# bmw.net
KiCad netlist of a schematic drawn in EAGLE
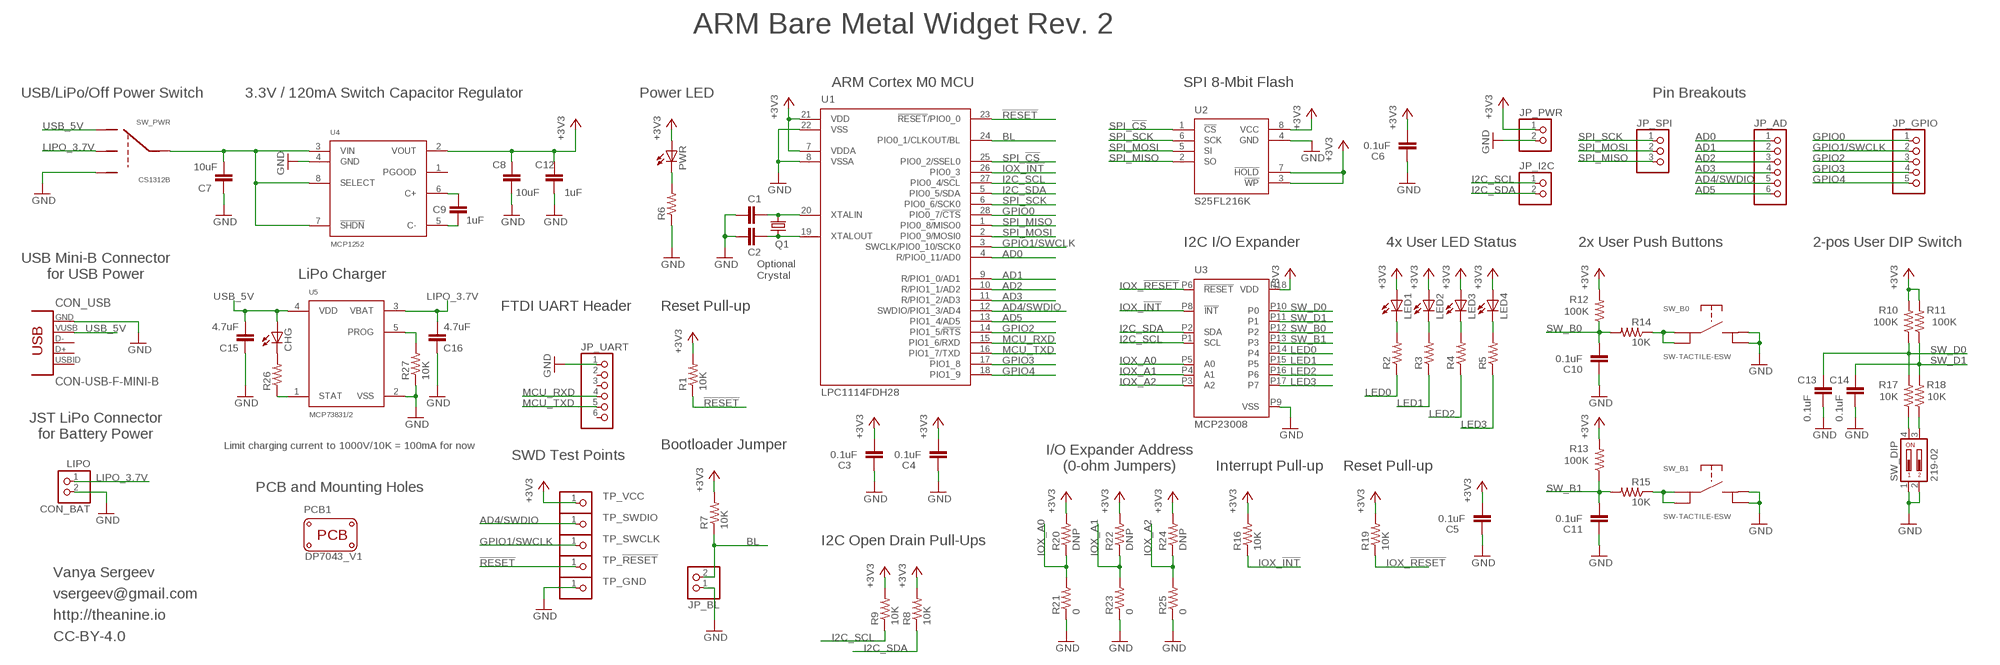
[diagram p0: schematic, sheet 1]

(export (version "E")
  (design (tool "Eeschema 10.0.6"))
  (components
    (comp (ref "C1")
      (value "C-EUC0805")
      (footprint "eagle-import:C0805")
      (libsource (lib "eagle-import") (part "C-EUC0805"))
    )
    (comp (ref "C2")
      (value "C-EUC0805")
      (footprint "eagle-import:C0805")
      (libsource (lib "eagle-import") (part "C-EUC0805"))
    )
    (comp (ref "C3")
      (value "0.1uF")
      (footprint "eagle-import:C0805")
      (libsource (lib "eagle-import") (part "C-EUC0805"))
    )
    (comp (ref "C4")
      (value "0.1uF")
      (footprint "eagle-import:C0805")
      (libsource (lib "eagle-import") (part "C-EUC0805"))
    )
    (comp (ref "C5")
      (value "0.1uF")
      (footprint "eagle-import:C0805")
      (libsource (lib "eagle-import") (part "C-EUC0805"))
    )
    (comp (ref "C6")
      (value "0.1uF")
      (footprint "eagle-import:C0805")
      (libsource (lib "eagle-import") (part "C-EUC0805"))
    )
    (comp (ref "C7")
      (value "10uF")
      (footprint "eagle-import:C1206")
      (libsource (lib "eagle-import") (part "C-EUC1206"))
    )
    (comp (ref "C8")
      (value "10uF")
      (footprint "eagle-import:C1206")
      (libsource (lib "eagle-import") (part "C-EUC1206"))
    )
    (comp (ref "C9")
      (value "1uF")
      (footprint "eagle-import:C0805")
      (libsource (lib "eagle-import") (part "C-EUC0805"))
    )
    (comp (ref "C10")
      (value "0.1uF")
      (footprint "eagle-import:C0805")
      (libsource (lib "eagle-import") (part "C-EUC0805"))
    )
    (comp (ref "C11")
      (value "0.1uF")
      (footprint "eagle-import:C0805")
      (libsource (lib "eagle-import") (part "C-EUC0805"))
    )
    (comp (ref "C12")
      (value "1uF")
      (footprint "eagle-import:C0805")
      (libsource (lib "eagle-import") (part "C-EUC0805"))
    )
    (comp (ref "C13")
      (value "0.1uF")
      (footprint "eagle-import:C0805")
      (libsource (lib "eagle-import") (part "C-EUC0805"))
    )
    (comp (ref "C14")
      (value "0.1uF")
      (footprint "eagle-import:C0805")
      (libsource (lib "eagle-import") (part "C-EUC0805"))
    )
    (comp (ref "C15")
      (value "4.7uF")
      (footprint "eagle-import:C0805")
      (libsource (lib "eagle-import") (part "C-EUC0805"))
    )
    (comp (ref "C16")
      (value "4.7uF")
      (footprint "eagle-import:C0805")
      (libsource (lib "eagle-import") (part "C-EUC0805"))
    )
    (comp (ref "CHG")
      (value "LEDCHIPLED_0805")
      (footprint "eagle-import:CHIPLED_0805")
      (libsource (lib "eagle-import") (part "LEDCHIPLED_0805"))
    )
    (comp (ref "CON_BAT")
      (value "LIPO")
      (footprint "eagle-import:JST-PH-2-SMT-RA")
      (libsource (lib "eagle-import") (part "JST_2PIN-SMT-RA"))
    )
    (comp (ref "CON_USB")
      (value "CON-USB-F-MINI-B")
      (footprint "eagle-import:CONN_USB_MINI-B")
      (libsource (lib "eagle-import") (part "CON-USB-F-MINI-B"))
    )
    (comp (ref "JP_AD")
      (value "PINHD-1X6")
      (footprint "eagle-import:1X06")
      (libsource (lib "eagle-import") (part "PINHD-1X6"))
    )
    (comp (ref "JP_BL")
      (value "PINHD-1X2")
      (footprint "eagle-import:1X02")
      (libsource (lib "eagle-import") (part "PINHD-1X2"))
    )
    (comp (ref "JP_GPIO")
      (value "PINHD-1X5")
      (footprint "eagle-import:1X05")
      (libsource (lib "eagle-import") (part "PINHD-1X5"))
    )
    (comp (ref "JP_I2C")
      (value "PINHD-1X2")
      (footprint "eagle-import:1X02")
      (libsource (lib "eagle-import") (part "PINHD-1X2"))
    )
    (comp (ref "JP_PWR")
      (value "PINHD-1X2")
      (footprint "eagle-import:1X02")
      (libsource (lib "eagle-import") (part "PINHD-1X2"))
    )
    (comp (ref "JP_SPI")
      (value "PINHD-1X3")
      (footprint "eagle-import:1X03")
      (libsource (lib "eagle-import") (part "PINHD-1X3"))
    )
    (comp (ref "JP_UART")
      (value "PINHD-1X6/90")
      (footprint "eagle-import:1X06_90")
      (libsource (lib "eagle-import") (part "PINHD-1X6/90"))
    )
    (comp (ref "LED1")
      (value "LEDCHIPLED_0805")
      (footprint "eagle-import:CHIPLED_0805")
      (libsource (lib "eagle-import") (part "LEDCHIPLED_0805"))
    )
    (comp (ref "LED2")
      (value "LEDCHIPLED_0805")
      (footprint "eagle-import:CHIPLED_0805")
      (libsource (lib "eagle-import") (part "LEDCHIPLED_0805"))
    )
    (comp (ref "LED3")
      (value "LEDCHIPLED_0805")
      (footprint "eagle-import:CHIPLED_0805")
      (libsource (lib "eagle-import") (part "LEDCHIPLED_0805"))
    )
    (comp (ref "LED4")
      (value "LEDCHIPLED_0805")
      (footprint "eagle-import:CHIPLED_0805")
      (libsource (lib "eagle-import") (part "LEDCHIPLED_0805"))
    )
    (comp (ref "PCB1")
      (value "PCB_DP_RECTANGLE-43X70")
      (footprint "eagle-import:DP7043_V1")
      (libsource (lib "eagle-import") (part "PCB_DP_RECTANGLE-43X70"))
    )
    (comp (ref "PWR")
      (value "LEDCHIPLED_0805")
      (footprint "eagle-import:CHIPLED_0805")
      (libsource (lib "eagle-import") (part "LEDCHIPLED_0805"))
    )
    (comp (ref "Q1")
      (value "CRYSTALHC49UP")
      (footprint "eagle-import:HC49UP")
      (libsource (lib "eagle-import") (part "CRYSTALHC49UP"))
    )
    (comp (ref "R1")
      (value "10K")
      (footprint "eagle-import:R0805")
      (libsource (lib "eagle-import") (part "R-US_R0805"))
    )
    (comp (ref "R2")
      (value "R-US_R0805")
      (footprint "eagle-import:R0805")
      (libsource (lib "eagle-import") (part "R-US_R0805"))
    )
    (comp (ref "R3")
      (value "R-US_R0805")
      (footprint "eagle-import:R0805")
      (libsource (lib "eagle-import") (part "R-US_R0805"))
    )
    (comp (ref "R4")
      (value "R-US_R0805")
      (footprint "eagle-import:R0805")
      (libsource (lib "eagle-import") (part "R-US_R0805"))
    )
    (comp (ref "R5")
      (value "R-US_R0805")
      (footprint "eagle-import:R0805")
      (libsource (lib "eagle-import") (part "R-US_R0805"))
    )
    (comp (ref "R6")
      (value "R-US_R0805")
      (footprint "eagle-import:R0805")
      (libsource (lib "eagle-import") (part "R-US_R0805"))
    )
    (comp (ref "R7")
      (value "10K")
      (footprint "eagle-import:R0805")
      (libsource (lib "eagle-import") (part "R-US_R0805"))
    )
    (comp (ref "R8")
      (value "10K")
      (footprint "eagle-import:R0805")
      (libsource (lib "eagle-import") (part "R-US_R0805"))
    )
    (comp (ref "R9")
      (value "10K")
      (footprint "eagle-import:R0805")
      (libsource (lib "eagle-import") (part "R-US_R0805"))
    )
    (comp (ref "R10")
      (value "100K")
      (footprint "eagle-import:R0805")
      (libsource (lib "eagle-import") (part "R-US_R0805"))
    )
    (comp (ref "R11")
      (value "100K")
      (footprint "eagle-import:R0805")
      (libsource (lib "eagle-import") (part "R-US_R0805"))
    )
    (comp (ref "R12")
      (value "100K")
      (footprint "eagle-import:R0805")
      (libsource (lib "eagle-import") (part "R-US_R0805"))
    )
    (comp (ref "R13")
      (value "100K")
      (footprint "eagle-import:R0805")
      (libsource (lib "eagle-import") (part "R-US_R0805"))
    )
    (comp (ref "R14")
      (value "10K")
      (footprint "eagle-import:R0805")
      (libsource (lib "eagle-import") (part "R-US_R0805"))
    )
    (comp (ref "R15")
      (value "10K")
      (footprint "eagle-import:R0805")
      (libsource (lib "eagle-import") (part "R-US_R0805"))
    )
    (comp (ref "R16")
      (value "10K")
      (footprint "eagle-import:R0805")
      (libsource (lib "eagle-import") (part "R-US_R0805"))
    )
    (comp (ref "R17")
      (value "10K")
      (footprint "eagle-import:R0805")
      (libsource (lib "eagle-import") (part "R-US_R0805"))
    )
    (comp (ref "R18")
      (value "10K")
      (footprint "eagle-import:R0805")
      (libsource (lib "eagle-import") (part "R-US_R0805"))
    )
    (comp (ref "R19")
      (value "10K")
      (footprint "eagle-import:R0805")
      (libsource (lib "eagle-import") (part "R-US_R0805"))
    )
    (comp (ref "R20")
      (value "DNP")
      (footprint "eagle-import:R0603")
      (libsource (lib "eagle-import") (part "R-US_R0603"))
    )
    (comp (ref "R21")
      (value "0")
      (footprint "eagle-import:R0603")
      (libsource (lib "eagle-import") (part "R-US_R0603"))
    )
    (comp (ref "R22")
      (value "DNP")
      (footprint "eagle-import:R0603")
      (libsource (lib "eagle-import") (part "R-US_R0603"))
    )
    (comp (ref "R23")
      (value "0")
      (footprint "eagle-import:R0603")
      (libsource (lib "eagle-import") (part "R-US_R0603"))
    )
    (comp (ref "R24")
      (value "DNP")
      (footprint "eagle-import:R0603")
      (libsource (lib "eagle-import") (part "R-US_R0603"))
    )
    (comp (ref "R25")
      (value "0")
      (footprint "eagle-import:R0603")
      (libsource (lib "eagle-import") (part "R-US_R0603"))
    )
    (comp (ref "R26")
      (value "R-US_R0805")
      (footprint "eagle-import:R0805")
      (libsource (lib "eagle-import") (part "R-US_R0805"))
    )
    (comp (ref "R27")
      (value "10K")
      (footprint "eagle-import:R0805")
      (libsource (lib "eagle-import") (part "R-US_R0805"))
    )
    (comp (ref "SW_B0")
      (value "SW-TACTILE-ESW")
      (footprint "eagle-import:SW-TACT-ESW")
      (libsource (lib "eagle-import") (part "SW-TACTILE-ESW"))
    )
    (comp (ref "SW_B1")
      (value "SW-TACTILE-ESW")
      (footprint "eagle-import:SW-TACT-ESW")
      (libsource (lib "eagle-import") (part "SW-TACTILE-ESW"))
    )
    (comp (ref "SW_DIP")
      (value "219-02")
      (footprint "eagle-import:CTS-219-02")
      (libsource (lib "eagle-import") (part "219-02"))
    )
    (comp (ref "SW_PWR")
      (value "CS1312B")
      (footprint "eagle-import:CS1312B")
      (libsource (lib "eagle-import") (part "CS1312B"))
    )
    (comp (ref "TP_!RESET")
      (value "PINHD-1X1")
      (footprint "eagle-import:1X01")
      (libsource (lib "eagle-import") (part "PINHD-1X1"))
    )
    (comp (ref "TP_GND")
      (value "PINHD-1X1")
      (footprint "eagle-import:1X01")
      (libsource (lib "eagle-import") (part "PINHD-1X1"))
    )
    (comp (ref "TP_SWCLK")
      (value "PINHD-1X1")
      (footprint "eagle-import:1X01")
      (libsource (lib "eagle-import") (part "PINHD-1X1"))
    )
    (comp (ref "TP_SWDIO")
      (value "PINHD-1X1")
      (footprint "eagle-import:1X01")
      (libsource (lib "eagle-import") (part "PINHD-1X1"))
    )
    (comp (ref "TP_VCC")
      (value "PINHD-1X1")
      (footprint "eagle-import:1X01")
      (libsource (lib "eagle-import") (part "PINHD-1X1"))
    )
    (comp (ref "U1")
      (value "LPC1114FDH28")
      (footprint "eagle-import:TSSOP28")
      (libsource (lib "eagle-import") (part "LPC1114FDH28"))
    )
    (comp (ref "U2")
      (value "S25FL216K")
      (footprint "eagle-import:SOIC127P600X175-8N")
      (libsource (lib "eagle-import") (part "S25FL208K"))
    )
    (comp (ref "U3")
      (value "MCP23008")
      (footprint "eagle-import:SOIC-18W")
      (libsource (lib "eagle-import") (part "MCP23008"))
    )
    (comp (ref "U4")
      (value "MCP1252")
      (footprint "eagle-import:MSOP8")
      (libsource (lib "eagle-import") (part "MCP1252"))
    )
    (comp (ref "U5")
      (value "MCP73831/2")
      (footprint "eagle-import:SOT23-5L")
      (libsource (lib "eagle-import") (part "MCP73831/2"))
    )
  )
  (nets
    (net (code "1") (name "+3V3") (class "Default")
      (node (ref "C12") (pin "2") (pinfunction "2_2") (pintype "passive"))
      (node (ref "C3") (pin "2") (pinfunction "2_2") (pintype "passive"))
      (node (ref "C4") (pin "2") (pinfunction "2_2") (pintype "passive"))
      (node (ref "C5") (pin "2") (pinfunction "2_2") (pintype "passive"))
      (node (ref "C6") (pin "2") (pinfunction "2_2") (pintype "passive"))
      (node (ref "C8") (pin "2") (pinfunction "2_2") (pintype "passive"))
      (node (ref "JP_PWR") (pin "1") (pinfunction "1_1") (pintype "passive"))
      (node (ref "LED1") (pin "A") (pinfunction "A_A") (pintype "passive"))
      (node (ref "LED2") (pin "A") (pinfunction "A_A") (pintype "passive"))
      (node (ref "LED3") (pin "A") (pinfunction "A_A") (pintype "passive"))
      (node (ref "LED4") (pin "A") (pinfunction "A_A") (pintype "passive"))
      (node (ref "PWR") (pin "A") (pinfunction "A_A") (pintype "passive"))
      (node (ref "R1") (pin "2") (pinfunction "2_2") (pintype "passive"))
      (node (ref "R10") (pin "2") (pinfunction "2_2") (pintype "passive"))
      (node (ref "R11") (pin "2") (pinfunction "2_2") (pintype "passive"))
      (node (ref "R12") (pin "2") (pinfunction "2_2") (pintype "passive"))
      (node (ref "R13") (pin "2") (pinfunction "2_2") (pintype "passive"))
      (node (ref "R16") (pin "2") (pinfunction "2_2") (pintype "passive"))
      (node (ref "R19") (pin "2") (pinfunction "2_2") (pintype "passive"))
      (node (ref "R20") (pin "2") (pinfunction "2_2") (pintype "passive"))
      (node (ref "R22") (pin "2") (pinfunction "2_2") (pintype "passive"))
      (node (ref "R24") (pin "2") (pinfunction "2_2") (pintype "passive"))
      (node (ref "R7") (pin "2") (pinfunction "2_2") (pintype "passive"))
      (node (ref "R8") (pin "2") (pinfunction "2_2") (pintype "passive"))
      (node (ref "R9") (pin "2") (pinfunction "2_2") (pintype "passive"))
      (node (ref "TP_VCC") (pin "1") (pinfunction "1_1") (pintype "passive"))
      (node (ref "U1") (pin "21") (pinfunction "VDD_21") (pintype "power_in"))
      (node (ref "U1") (pin "7") (pinfunction "VDDA_7") (pintype "power_in"))
      (node (ref "U2") (pin "3") (pinfunction "~{WP}_3") (pintype "bidirectional"))
      (node (ref "U2") (pin "7") (pinfunction "~{HOLD}_7") (pintype "bidirectional"))
      (node (ref "U2") (pin "8") (pinfunction "VCC_8") (pintype "power_in"))
      (node (ref "U3") (pin "P18") (pinfunction "VDD_P18") (pintype "power_in"))
      (node (ref "U4") (pin "2") (pinfunction "VOUT_2") (pintype "power_in"))
    )
    (net (code "2") (name "/AD0") (class "Default")
      (node (ref "JP_AD") (pin "1") (pinfunction "1_1") (pintype "passive"))
      (node (ref "U1") (pin "4") (pinfunction "R/PIO0_11/AD0_4") (pintype "bidirectional"))
    )
    (net (code "3") (name "/AD1") (class "Default")
      (node (ref "JP_AD") (pin "2") (pinfunction "2_2") (pintype "passive"))
      (node (ref "U1") (pin "9") (pinfunction "R/PIO1_0/AD1_9") (pintype "bidirectional"))
    )
    (net (code "4") (name "/AD2") (class "Default")
      (node (ref "JP_AD") (pin "3") (pinfunction "3_3") (pintype "passive"))
      (node (ref "U1") (pin "10") (pinfunction "R/PIO1_1/AD2_10") (pintype "bidirectional"))
    )
    (net (code "5") (name "/AD3") (class "Default")
      (node (ref "JP_AD") (pin "4") (pinfunction "4_4") (pintype "passive"))
      (node (ref "U1") (pin "11") (pinfunction "R/PIO1_2/AD3_11") (pintype "bidirectional"))
    )
    (net (code "6") (name "/AD4{slash}SWDIO") (class "Default")
      (node (ref "JP_AD") (pin "5") (pinfunction "5_5") (pintype "passive"))
      (node (ref "TP_SWDIO") (pin "1") (pinfunction "1_1") (pintype "passive"))
      (node (ref "U1") (pin "12") (pinfunction "SWDIO/PIO1_3/AD4_12") (pintype "bidirectional"))
    )
    (net (code "7") (name "/AD5") (class "Default")
      (node (ref "JP_AD") (pin "6") (pinfunction "6_6") (pintype "passive"))
      (node (ref "U1") (pin "13") (pinfunction "PIO1_4/AD5_13") (pintype "bidirectional"))
    )
    (net (code "8") (name "/BL") (class "Default")
      (node (ref "JP_BL") (pin "2") (pinfunction "2_2") (pintype "passive"))
      (node (ref "R7") (pin "1") (pinfunction "1_1") (pintype "passive"))
      (node (ref "U1") (pin "24") (pinfunction "PIO0_1/CLKOUT/BL_24") (pintype "bidirectional"))
    )
    (net (code "9") (name "/GPIO0") (class "Default")
      (node (ref "JP_GPIO") (pin "1") (pinfunction "1_1") (pintype "passive"))
      (node (ref "U1") (pin "28") (pinfunction "PIO0_7/~{CTS}_28") (pintype "bidirectional"))
    )
    (net (code "10") (name "/GPIO1{slash}SWCLK") (class "Default")
      (node (ref "JP_GPIO") (pin "2") (pinfunction "2_2") (pintype "passive"))
      (node (ref "TP_SWCLK") (pin "1") (pinfunction "1_1") (pintype "passive"))
      (node (ref "U1") (pin "3") (pinfunction "SWCLK/PIO0_10/SCK0_3") (pintype "bidirectional"))
    )
    (net (code "11") (name "/GPIO2") (class "Default")
      (node (ref "JP_GPIO") (pin "3") (pinfunction "3_3") (pintype "passive"))
      (node (ref "U1") (pin "14") (pinfunction "PIO1_5/~{RTS}_14") (pintype "bidirectional"))
    )
    (net (code "12") (name "/GPIO3") (class "Default")
      (node (ref "JP_GPIO") (pin "4") (pinfunction "4_4") (pintype "passive"))
      (node (ref "U1") (pin "17") (pinfunction "PIO1_8_17") (pintype "bidirectional"))
    )
    (net (code "13") (name "/GPIO4") (class "Default")
      (node (ref "JP_GPIO") (pin "5") (pinfunction "5_5") (pintype "passive"))
      (node (ref "U1") (pin "18") (pinfunction "PIO1_9_18") (pintype "bidirectional"))
    )
    (net (code "14") (name "/I2C_SCL") (class "Default")
      (node (ref "JP_I2C") (pin "1") (pinfunction "1_1") (pintype "passive"))
      (node (ref "R9") (pin "1") (pinfunction "1_1") (pintype "passive"))
      (node (ref "U1") (pin "27") (pinfunction "PIO0_4/SCL_27") (pintype "bidirectional"))
      (node (ref "U3") (pin "P1") (pinfunction "SCL_P1") (pintype "input"))
    )
    (net (code "15") (name "/I2C_SDA") (class "Default")
      (node (ref "JP_I2C") (pin "2") (pinfunction "2_2") (pintype "passive"))
      (node (ref "R8") (pin "1") (pinfunction "1_1") (pintype "passive"))
      (node (ref "U1") (pin "5") (pinfunction "PIO0_5/SDA_5") (pintype "bidirectional"))
      (node (ref "U3") (pin "P2") (pinfunction "SDA_P2") (pintype "bidirectional"))
    )
    (net (code "16") (name "/IOX_A0") (class "Default")
      (node (ref "R20") (pin "1") (pinfunction "1_1") (pintype "passive"))
      (node (ref "R21") (pin "2") (pinfunction "2_2") (pintype "passive"))
      (node (ref "U3") (pin "P5") (pinfunction "A0_P5") (pintype "input"))
    )
    (net (code "17") (name "/IOX_A1") (class "Default")
      (node (ref "R22") (pin "1") (pinfunction "1_1") (pintype "passive"))
      (node (ref "R23") (pin "2") (pinfunction "2_2") (pintype "passive"))
      (node (ref "U3") (pin "P4") (pinfunction "A1_P4") (pintype "input"))
    )
    (net (code "18") (name "/IOX_A2") (class "Default")
      (node (ref "R24") (pin "1") (pinfunction "1_1") (pintype "passive"))
      (node (ref "R25") (pin "2") (pinfunction "2_2") (pintype "passive"))
      (node (ref "U3") (pin "P3") (pinfunction "A2_P3") (pintype "input"))
    )
    (net (code "19") (name "/IOX_~{INT}") (class "Default")
      (node (ref "R16") (pin "1") (pinfunction "1_1") (pintype "passive"))
      (node (ref "U1") (pin "26") (pinfunction "PIO0_3_26") (pintype "bidirectional"))
      (node (ref "U3") (pin "P8") (pinfunction "~{INT}_P8") (pintype "output"))
    )
    (net (code "20") (name "/IOX_~{RESET}") (class "Default")
      (node (ref "R19") (pin "1") (pinfunction "1_1") (pintype "passive"))
      (node (ref "U3") (pin "P6") (pinfunction "~{RESET}_P6") (pintype "output"))
    )
    (net (code "21") (name "/LED0") (class "Default")
      (node (ref "R2") (pin "1") (pinfunction "1_1") (pintype "passive"))
      (node (ref "U3") (pin "P14") (pinfunction "P4_P14") (pintype "bidirectional"))
    )
    (net (code "22") (name "/LED1") (class "Default")
      (node (ref "R3") (pin "1") (pinfunction "1_1") (pintype "passive"))
      (node (ref "U3") (pin "P15") (pinfunction "P5_P15") (pintype "bidirectional"))
    )
    (net (code "23") (name "/LED2") (class "Default")
      (node (ref "R4") (pin "1") (pinfunction "1_1") (pintype "passive"))
      (node (ref "U3") (pin "P16") (pinfunction "P6_P16") (pintype "bidirectional"))
    )
    (net (code "24") (name "/LED3") (class "Default")
      (node (ref "R5") (pin "1") (pinfunction "1_1") (pintype "passive"))
      (node (ref "U3") (pin "P17") (pinfunction "P7_P17") (pintype "bidirectional"))
    )
    (net (code "25") (name "/LIPO_3.7V") (class "Default")
      (node (ref "C16") (pin "2") (pinfunction "2_2") (pintype "passive"))
      (node (ref "CON_BAT") (pin "1") (pinfunction "2_1") (pintype "passive"))
      (node (ref "SW_PWR") (pin "P2") (pinfunction "2_P2") (pintype "bidirectional"))
      (node (ref "U5") (pin "3") (pinfunction "VBAT_3") (pintype "bidirectional"))
    )
    (net (code "26") (name "/MCU_RXD") (class "Default")
      (node (ref "JP_UART") (pin "4") (pinfunction "4_4") (pintype "passive"))
      (node (ref "U1") (pin "15") (pinfunction "PIO1_6/RXD_15") (pintype "bidirectional"))
    )
    (net (code "27") (name "/MCU_TXD") (class "Default")
      (node (ref "JP_UART") (pin "5") (pinfunction "5_5") (pintype "passive"))
      (node (ref "U1") (pin "16") (pinfunction "PIO1_7/TXD_16") (pintype "bidirectional"))
    )
    (net (code "28") (name "/SPI_MISO") (class "Default")
      (node (ref "JP_SPI") (pin "3") (pinfunction "3_3") (pintype "passive"))
      (node (ref "U1") (pin "1") (pinfunction "PIO0_8/MISO0_1") (pintype "bidirectional"))
      (node (ref "U2") (pin "2") (pinfunction "SO_2") (pintype "bidirectional"))
    )
    (net (code "29") (name "/SPI_MOSI") (class "Default")
      (node (ref "JP_SPI") (pin "2") (pinfunction "2_2") (pintype "passive"))
      (node (ref "U1") (pin "2") (pinfunction "PIO0_9/MOSI0_2") (pintype "bidirectional"))
      (node (ref "U2") (pin "5") (pinfunction "SI_5") (pintype "output"))
    )
    (net (code "30") (name "/SPI_SCK") (class "Default")
      (node (ref "JP_SPI") (pin "1") (pinfunction "1_1") (pintype "passive"))
      (node (ref "U1") (pin "6") (pinfunction "PIO0_6/SCK0_6") (pintype "bidirectional"))
      (node (ref "U2") (pin "6") (pinfunction "SCK_6") (pintype "input"))
    )
    (net (code "31") (name "/SPI_~{CS}") (class "Default")
      (node (ref "U1") (pin "25") (pinfunction "PIO0_2/SSEL0_25") (pintype "bidirectional"))
      (node (ref "U2") (pin "1") (pinfunction "~{CS}_1") (pintype "input"))
    )
    (net (code "32") (name "/SW_B0") (class "Default")
      (node (ref "C10") (pin "2") (pinfunction "2_2") (pintype "passive"))
      (node (ref "R12") (pin "1") (pinfunction "1_1") (pintype "passive"))
      (node (ref "R14") (pin "2") (pinfunction "2_2") (pintype "passive"))
      (node (ref "U3") (pin "P12") (pinfunction "P2_P12") (pintype "bidirectional"))
    )
    (net (code "33") (name "/SW_B1") (class "Default")
      (node (ref "C11") (pin "2") (pinfunction "2_2") (pintype "passive"))
      (node (ref "R13") (pin "1") (pinfunction "1_1") (pintype "passive"))
      (node (ref "R15") (pin "2") (pinfunction "2_2") (pintype "passive"))
      (node (ref "U3") (pin "P13") (pinfunction "P3_P13") (pintype "bidirectional"))
    )
    (net (code "34") (name "/SW_D0") (class "Default")
      (node (ref "C13") (pin "1") (pinfunction "1_1") (pintype "passive"))
      (node (ref "R10") (pin "1") (pinfunction "1_1") (pintype "passive"))
      (node (ref "R17") (pin "2") (pinfunction "2_2") (pintype "passive"))
      (node (ref "U3") (pin "P10") (pinfunction "P0_P10") (pintype "bidirectional"))
    )
    (net (code "35") (name "/SW_D1") (class "Default")
      (node (ref "C14") (pin "1") (pinfunction "1_1") (pintype "passive"))
      (node (ref "R11") (pin "1") (pinfunction "1_1") (pintype "passive"))
      (node (ref "R18") (pin "2") (pinfunction "2_2") (pintype "passive"))
      (node (ref "U3") (pin "P11") (pinfunction "P1_P11") (pintype "bidirectional"))
    )
    (net (code "36") (name "/USB_5V") (class "Default")
      (node (ref "C15") (pin "2") (pinfunction "2_2") (pintype "passive"))
      (node (ref "CHG") (pin "A") (pinfunction "A_A") (pintype "passive"))
      (node (ref "CON_USB") (pin "VUSB") (pinfunction "VUSB_VUSB") (pintype "bidirectional"))
      (node (ref "SW_PWR") (pin "P1") (pinfunction "1_P1") (pintype "bidirectional"))
      (node (ref "U5") (pin "4") (pinfunction "VDD_4") (pintype "bidirectional"))
    )
    (net (code "37") (name "/~{RESET}") (class "Default")
      (node (ref "R1") (pin "1") (pinfunction "1_1") (pintype "passive"))
      (node (ref "TP_!RESET") (pin "1") (pinfunction "1_1") (pintype "passive"))
      (node (ref "U1") (pin "23") (pinfunction "~{RESET}/PIO0_0_23") (pintype "bidirectional"))
    )
    (net (code "38") (name "GND") (class "Default")
      (node (ref "C1") (pin "1") (pinfunction "1_1") (pintype "passive"))
      (node (ref "C10") (pin "1") (pinfunction "1_1") (pintype "passive"))
      (node (ref "C11") (pin "1") (pinfunction "1_1") (pintype "passive"))
      (node (ref "C12") (pin "1") (pinfunction "1_1") (pintype "passive"))
      (node (ref "C13") (pin "2") (pinfunction "2_2") (pintype "passive"))
      (node (ref "C14") (pin "2") (pinfunction "2_2") (pintype "passive"))
      (node (ref "C15") (pin "1") (pinfunction "1_1") (pintype "passive"))
      (node (ref "C16") (pin "1") (pinfunction "1_1") (pintype "passive"))
      (node (ref "C2") (pin "1") (pinfunction "1_1") (pintype "passive"))
      (node (ref "C3") (pin "1") (pinfunction "1_1") (pintype "passive"))
      (node (ref "C4") (pin "1") (pinfunction "1_1") (pintype "passive"))
      (node (ref "C5") (pin "1") (pinfunction "1_1") (pintype "passive"))
      (node (ref "C6") (pin "1") (pinfunction "1_1") (pintype "passive"))
      (node (ref "C7") (pin "1") (pinfunction "1_1") (pintype "passive"))
      (node (ref "C8") (pin "1") (pinfunction "1_1") (pintype "passive"))
      (node (ref "CON_BAT") (pin "2") (pinfunction "1_2") (pintype "passive"))
      (node (ref "CON_USB") (pin "GND") (pinfunction "GND_GND") (pintype "bidirectional"))
      (node (ref "JP_BL") (pin "1") (pinfunction "1_1") (pintype "passive"))
      (node (ref "JP_PWR") (pin "2") (pinfunction "2_2") (pintype "passive"))
      (node (ref "JP_UART") (pin "1") (pinfunction "1_1") (pintype "passive"))
      (node (ref "R21") (pin "1") (pinfunction "1_1") (pintype "passive"))
      (node (ref "R23") (pin "1") (pinfunction "1_1") (pintype "passive"))
      (node (ref "R25") (pin "1") (pinfunction "1_1") (pintype "passive"))
      (node (ref "R27") (pin "1") (pinfunction "1_1") (pintype "passive"))
      (node (ref "R6") (pin "1") (pinfunction "1_1") (pintype "passive"))
      (node (ref "SW_B0") (pin "P3") (pinfunction "P3_P3") (pintype "bidirectional"))
      (node (ref "SW_B0") (pin "P4") (pinfunction "P4_P4") (pintype "bidirectional"))
      (node (ref "SW_B1") (pin "P3") (pinfunction "P3_P3") (pintype "bidirectional"))
      (node (ref "SW_B1") (pin "P4") (pinfunction "P4_P4") (pintype "bidirectional"))
      (node (ref "SW_DIP") (pin "1") (pinfunction "1_1") (pintype "passive"))
      (node (ref "SW_DIP") (pin "2") (pinfunction "2_2") (pintype "passive"))
      (node (ref "SW_PWR") (pin "P4") (pinfunction "3_P4") (pintype "bidirectional"))
      (node (ref "TP_GND") (pin "1") (pinfunction "1_1") (pintype "passive"))
      (node (ref "U1") (pin "22") (pinfunction "VSS_22") (pintype "power_in"))
      (node (ref "U1") (pin "8") (pinfunction "VSSA_8") (pintype "power_in"))
      (node (ref "U2") (pin "4") (pinfunction "GND_4") (pintype "passive"))
      (node (ref "U3") (pin "P9") (pinfunction "VSS_P9") (pintype "power_in"))
      (node (ref "U4") (pin "4") (pinfunction "GND_4") (pintype "passive"))
      (node (ref "U5") (pin "2") (pinfunction "VSS_2") (pintype "bidirectional"))
    )
    (net (code "39") (name "Net-(CHG-PadC)") (class "Default")
      (node (ref "CHG") (pin "C") (pinfunction "C_C") (pintype "passive"))
      (node (ref "R26") (pin "2") (pinfunction "2_2") (pintype "passive"))
    )
    (net (code "40") (name "Net-(LED1-PadC)") (class "Default")
      (node (ref "LED1") (pin "C") (pinfunction "C_C") (pintype "passive"))
      (node (ref "R2") (pin "2") (pinfunction "2_2") (pintype "passive"))
    )
    (net (code "41") (name "Net-(LED2-PadC)") (class "Default")
      (node (ref "LED2") (pin "C") (pinfunction "C_C") (pintype "passive"))
      (node (ref "R3") (pin "2") (pinfunction "2_2") (pintype "passive"))
    )
    (net (code "42") (name "Net-(LED3-PadC)") (class "Default")
      (node (ref "LED3") (pin "C") (pinfunction "C_C") (pintype "passive"))
      (node (ref "R4") (pin "2") (pinfunction "2_2") (pintype "passive"))
    )
    (net (code "43") (name "Net-(LED4-PadC)") (class "Default")
      (node (ref "LED4") (pin "C") (pinfunction "C_C") (pintype "passive"))
      (node (ref "R5") (pin "2") (pinfunction "2_2") (pintype "passive"))
    )
    (net (code "44") (name "Net-(PWR-PadC)") (class "Default")
      (node (ref "PWR") (pin "C") (pinfunction "C_C") (pintype "passive"))
      (node (ref "R6") (pin "2") (pinfunction "2_2") (pintype "passive"))
    )
    (net (code "45") (name "Net-(R14-Pad1)") (class "Default")
      (node (ref "R14") (pin "1") (pinfunction "1_1") (pintype "passive"))
      (node (ref "SW_B0") (pin "P1") (pinfunction "P1_P1") (pintype "bidirectional"))
      (node (ref "SW_B0") (pin "P2") (pinfunction "P2_P2") (pintype "bidirectional"))
    )
    (net (code "46") (name "Net-(R15-Pad1)") (class "Default")
      (node (ref "R15") (pin "1") (pinfunction "1_1") (pintype "passive"))
      (node (ref "SW_B1") (pin "P1") (pinfunction "P1_P1") (pintype "bidirectional"))
      (node (ref "SW_B1") (pin "P2") (pinfunction "P2_P2") (pintype "bidirectional"))
    )
    (net (code "47") (name "Net-(R17-Pad1)") (class "Default")
      (node (ref "R17") (pin "1") (pinfunction "1_1") (pintype "passive"))
      (node (ref "SW_DIP") (pin "4") (pinfunction "4_4") (pintype "passive"))
    )
    (net (code "48") (name "Net-(R18-Pad1)") (class "Default")
      (node (ref "R18") (pin "1") (pinfunction "1_1") (pintype "passive"))
      (node (ref "SW_DIP") (pin "3") (pinfunction "3_3") (pintype "passive"))
    )
    (net (code "49") (name "Net-(SW_PWR-C)") (class "Default")
      (node (ref "C7") (pin "2") (pinfunction "2_2") (pintype "passive"))
      (node (ref "SW_PWR") (pin "P3") (pinfunction "C_P3") (pintype "bidirectional"))
      (node (ref "U4") (pin "3") (pinfunction "VIN_3") (pintype "power_in"))
      (node (ref "U4") (pin "7") (pinfunction "~{SHDN}_7") (pintype "bidirectional"))
      (node (ref "U4") (pin "8") (pinfunction "SELECT_8") (pintype "bidirectional"))
    )
    (net (code "50") (name "Net-(U1-XTALIN)") (class "Default")
      (node (ref "C1") (pin "2") (pinfunction "2_2") (pintype "passive"))
      (node (ref "Q1") (pin "2") (pinfunction "2_2") (pintype "passive"))
      (node (ref "U1") (pin "20") (pinfunction "XTALIN_20") (pintype "passive"))
    )
    (net (code "51") (name "Net-(U1-XTALOUT)") (class "Default")
      (node (ref "C2") (pin "2") (pinfunction "2_2") (pintype "passive"))
      (node (ref "Q1") (pin "1") (pinfunction "1_1") (pintype "passive"))
      (node (ref "U1") (pin "19") (pinfunction "XTALOUT_19") (pintype "passive"))
    )
    (net (code "52") (name "Net-(U4-C+)") (class "Default")
      (node (ref "C9") (pin "2") (pinfunction "2_2") (pintype "passive"))
      (node (ref "U4") (pin "6") (pinfunction "C+_6") (pintype "passive"))
    )
    (net (code "53") (name "Net-(U4-C-)") (class "Default")
      (node (ref "C9") (pin "1") (pinfunction "1_1") (pintype "passive"))
      (node (ref "U4") (pin "5") (pinfunction "C-_5") (pintype "passive"))
    )
    (net (code "54") (name "Net-(U5-PROG)") (class "Default")
      (node (ref "R27") (pin "2") (pinfunction "2_2") (pintype "passive"))
      (node (ref "U5") (pin "5") (pinfunction "PROG_5") (pintype "bidirectional"))
    )
    (net (code "55") (name "Net-(U5-STAT)") (class "Default")
      (node (ref "R26") (pin "1") (pinfunction "1_1") (pintype "passive"))
      (node (ref "U5") (pin "1") (pinfunction "STAT_1") (pintype "bidirectional"))
    )
    (net (code "56") (name "unconnected-(CON_USB-PadD+)") (class "Default")
      (node (ref "CON_USB") (pin "D+") (pinfunction "D+_D+") (pintype "bidirectional"))
    )
    (net (code "57") (name "unconnected-(CON_USB-PadD-)") (class "Default")
      (node (ref "CON_USB") (pin "D-") (pinfunction "D-_D-") (pintype "bidirectional"))
    )
    (net (code "58") (name "unconnected-(CON_USBB-USBID-PadID)") (class "Default")
      (node (ref "CON_USB") (pin "ID") (pinfunction "USBID_ID") (pintype "bidirectional"))
    )
    (net (code "59") (name "unconnected-(JP_UART-Pad2)") (class "Default")
      (node (ref "JP_UART") (pin "2") (pinfunction "2_2") (pintype "passive"))
    )
    (net (code "60") (name "unconnected-(JP_UART-Pad3)") (class "Default")
      (node (ref "JP_UART") (pin "3") (pinfunction "3_3") (pintype "passive"))
    )
    (net (code "61") (name "unconnected-(JP_UART-Pad6)") (class "Default")
      (node (ref "JP_UART") (pin "6") (pinfunction "6_6") (pintype "passive"))
    )
    (net (code "62") (name "unconnected-(U4-PGOOD-Pad1)") (class "Default")
      (node (ref "U4") (pin "1") (pinfunction "PGOOD_1") (pintype "bidirectional"))
    )
  )
)
